# FingerBase.net
KiCad netlist of a schematic drawn in Altium Designer
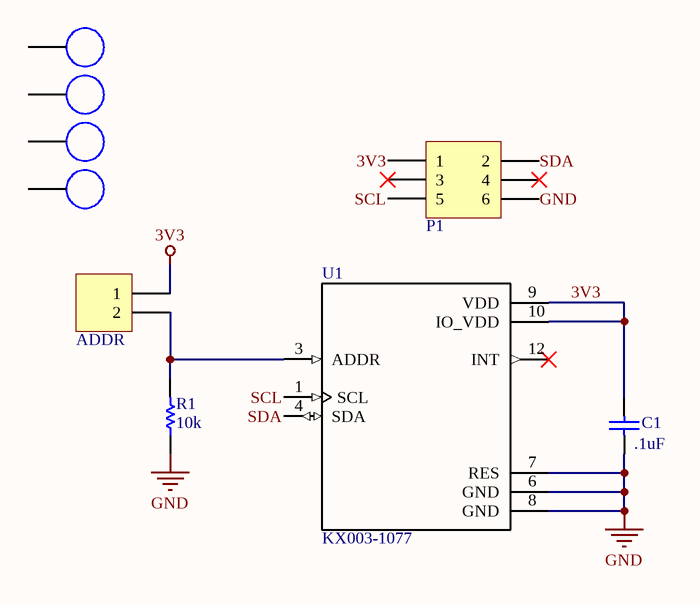
[diagram p0: FingerBase.SchDoc]

(export (version "E")
  (design (tool "Eeschema 10.0.6"))
  (components
    (comp (ref "ADDR")
      (value "90120-0122")
      (footprint "HDR1X2")
      (description "MOLEX CONN HEADER 2POS .100\" STR TIN")
      (libsource (lib "AltiumGFU64") (part "Header 2"))
    )
    (comp (ref "C1")
      (value ".1uF")
      (footprint "0805")
      (description ".1, 10%, 50V")
      (fields (field (name "GFUPARTNO") "CL21A475KPFNNNE"))
      (libsource (lib "AltiumGFU64") (part "Cap"))
    )
    (comp (ref "DR1")
      (value "4-40 DRILL HOLE")
      (footprint "4_40 DRILL HOLE")
      (description "Mounting hole for 4-40 screw, non-BOM")
      (fields (field (name "GFUPARTNO") "4_40 DRILL HOLE"))
      (libsource (lib "AltiumGFU64") (part "8_32 DRILL HOLE"))
    )
    (comp (ref "DR2")
      (value "4-40 DRILL HOLE")
      (footprint "4_40 DRILL HOLE")
      (description "Mounting hole for 4-40 screw, non-BOM")
      (fields (field (name "GFUPARTNO") "4_40 DRILL HOLE"))
      (libsource (lib "AltiumGFU64") (part "8_32 DRILL HOLE"))
    )
    (comp (ref "DR3")
      (value "4-40 DRILL HOLE")
      (footprint "4_40 DRILL HOLE")
      (description "Mounting hole for 4-40 screw, non-BOM")
      (fields (field (name "GFUPARTNO") "4_40 DRILL HOLE"))
      (libsource (lib "AltiumGFU64") (part "8_32 DRILL HOLE"))
    )
    (comp (ref "DR4")
      (value "4-40 DRILL HOLE")
      (footprint "4_40 DRILL HOLE")
      (description "Mounting hole for 4-40 screw, non-BOM")
      (fields (field (name "GFUPARTNO") "4_40 DRILL HOLE"))
      (libsource (lib "AltiumGFU64") (part "8_32 DRILL HOLE"))
    )
    (comp (ref "P1")
      (value "90131-0123")
      (footprint "HDR2X3")
      (description "MOLEX CONN HEADER 6POS 2ROW .100\" STR TIN")
      (libsource (lib "AltiumGFU64") (part "Header 3X2"))
    )
    (comp (ref "R1")
      (value "10k")
      (footprint "0805_RES_HD")
      (description "RES 10K OHM 1/8W 5% 0805")
      (fields (field (name "GFUPARTNO") "RC2012F752CS"))
      (libsource (lib "AltiumGFU64") (part "ResBasic"))
    )
    (comp (ref "U1")
      (value "KX003-1077")
      (footprint "*XDCR_KX003-1077")
      (description "Accelerometer X, Y, Z Axis Â±2g, 4g, 8g, 16g 3.5kHz _X,Y_, 1.8kHz _Z_ 12-LGA _2x2_")
      (fields
        (field (name "DIGI-KEY_PART_NUMBER") "KX003-1077CT-ND")
        (field (name "MF") "Rohm Semiconductor")
      )
      (libsource (lib "KX003-1077") (part "KX003-1077"))
    )
  )
  (nets
    (net (code "1") (name "/SCL") (class "Default")
      (node (ref "P1") (pin "5") (pinfunction "5_5") (pintype "passive"))
      (node (ref "U1") (pin "1") (pinfunction "SCL_1") (pintype "input"))
    )
    (net (code "2") (name "/SDA") (class "Default")
      (node (ref "P1") (pin "2") (pinfunction "2_2") (pintype "passive"))
      (node (ref "U1") (pin "4") (pinfunction "SDA_4") (pintype "bidirectional"))
    )
    (net (code "3") (name "3V3") (class "Default")
      (node (ref "ADDR") (pin "1") (pinfunction "1_1") (pintype "passive"))
      (node (ref "C1") (pin "2") (pinfunction "2_2") (pintype "passive"))
      (node (ref "P1") (pin "1") (pinfunction "1_1") (pintype "passive"))
      (node (ref "U1") (pin "10") (pinfunction "IO_VDD_10") (pintype "power_in"))
      (node (ref "U1") (pin "9") (pinfunction "VDD_9") (pintype "power_in"))
    )
    (net (code "4") (name "GND") (class "Default")
      (node (ref "C1") (pin "1") (pinfunction "1_1") (pintype "passive"))
      (node (ref "P1") (pin "6") (pinfunction "6_6") (pintype "passive"))
      (node (ref "R1") (pin "1") (pinfunction "1_1") (pintype "passive"))
      (node (ref "U1") (pin "6") (pinfunction "GND_6") (pintype "power_in"))
      (node (ref "U1") (pin "7") (pinfunction "RES_7") (pintype "power_in"))
      (node (ref "U1") (pin "8") (pinfunction "GND_8") (pintype "power_in"))
    )
    (net (code "5") (name "Net-(U1-ADDR)") (class "Default")
      (node (ref "ADDR") (pin "2") (pinfunction "2_2") (pintype "passive"))
      (node (ref "R1") (pin "2") (pinfunction "2_2") (pintype "passive"))
      (node (ref "U1") (pin "3") (pinfunction "ADDR_3") (pintype "input"))
    )
    (net (code "6") (name "unconnected-(DR1-Pad0)") (class "Default")
      (node (ref "DR1") (pin "0") (pinfunction "0_0") (pintype "passive"))
    )
    (net (code "7") (name "unconnected-(DR2-Pad0)") (class "Default")
      (node (ref "DR2") (pin "0") (pinfunction "0_0") (pintype "passive"))
    )
    (net (code "8") (name "unconnected-(DR3-Pad0)") (class "Default")
      (node (ref "DR3") (pin "0") (pinfunction "0_0") (pintype "passive"))
    )
    (net (code "9") (name "unconnected-(DR4-Pad0)") (class "Default")
      (node (ref "DR4") (pin "0") (pinfunction "0_0") (pintype "passive"))
    )
    (net (code "10") (name "unconnected-(P1-Pad3)") (class "Default")
      (node (ref "P1") (pin "3") (pinfunction "3_3") (pintype "passive+no_connect"))
    )
    (net (code "11") (name "unconnected-(P1-Pad4)") (class "Default")
      (node (ref "P1") (pin "4") (pinfunction "4_4") (pintype "passive+no_connect"))
    )
    (net (code "12") (name "unconnected-(U1-INT-Pad12)") (class "Default")
      (node (ref "U1") (pin "12") (pinfunction "INT_12") (pintype "output+no_connect"))
    )
  )
)
